# SCH_pcb_tfg_v1_1a_conHDR_2021-07-26.net
KiCad netlist of a schematic drawn in EasyEDA
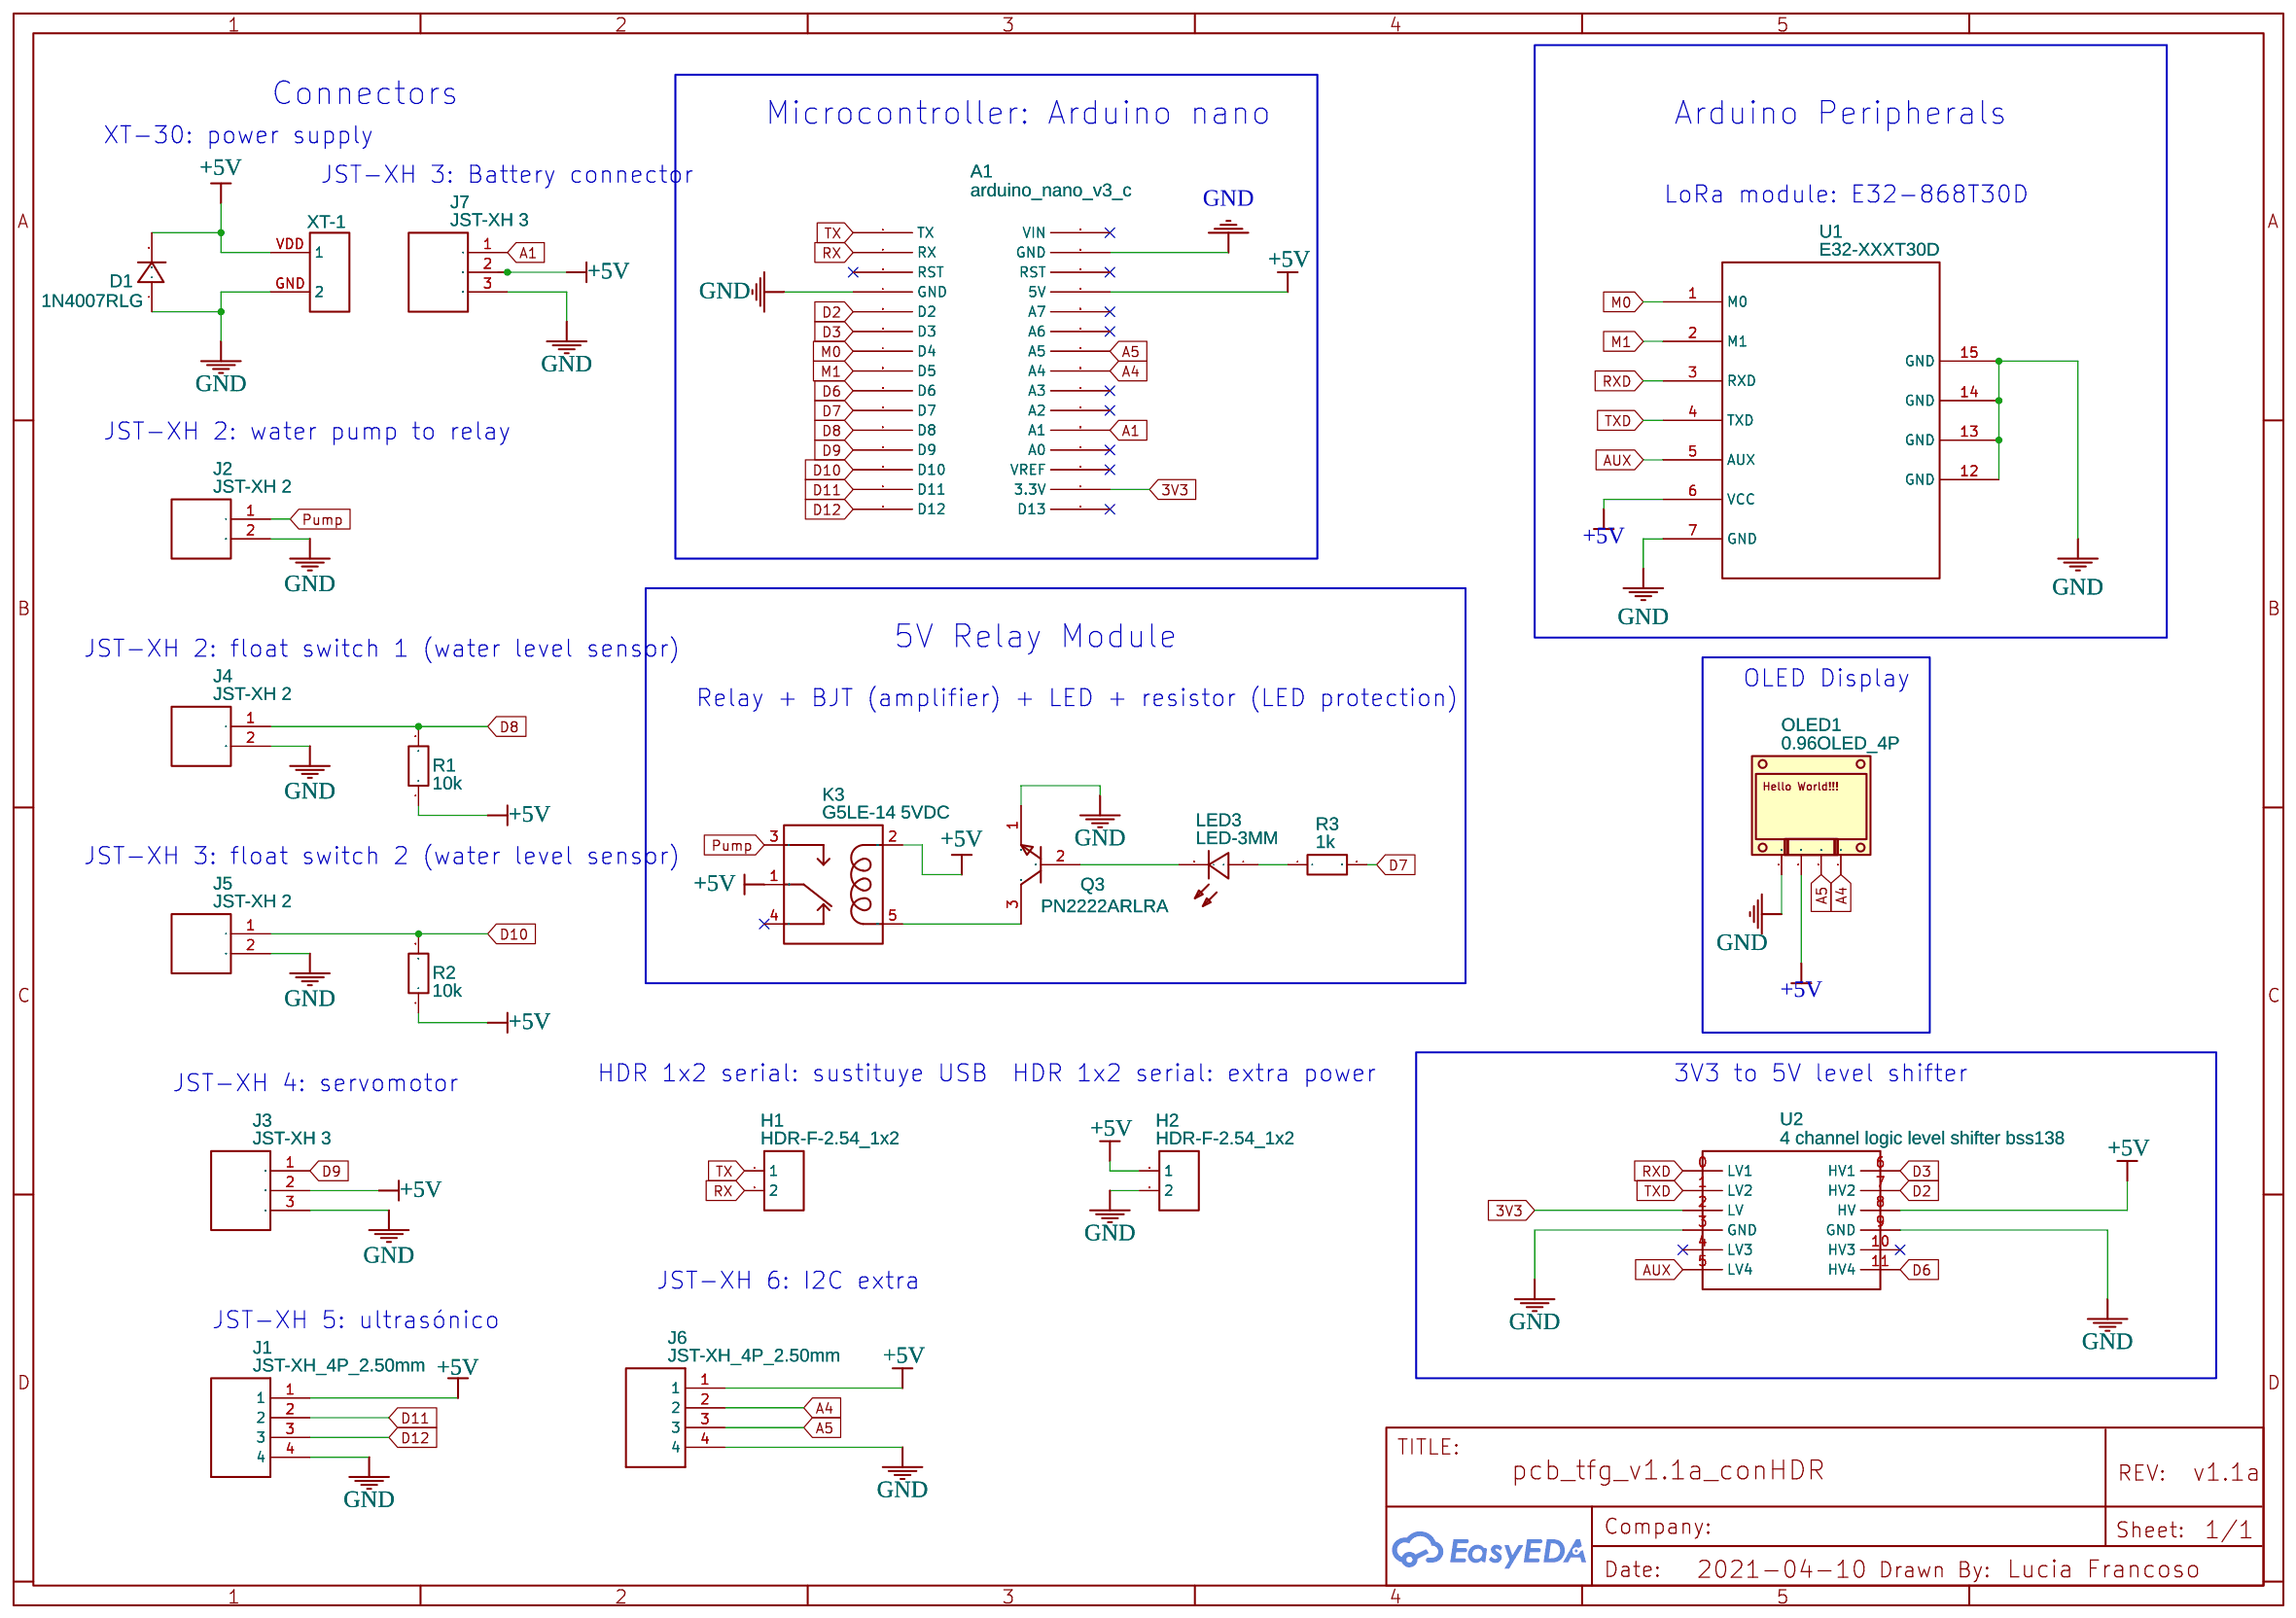
[diagram p0: schematic sheet]

(export (version "E")
  (design (tool "Eeschema 10.0.6"))
  (components
    (comp (ref "A1")
      (value "arduino_nano_v3_с")
      (fields (field (name "BOM_Manufacturer Part") "Arduino Nano"))
      (libsource (lib "") (part "arduino_nano_v3_с"))
    )
    (comp (ref "D1")
      (value "1N4007RLG")
      (fields (field (name "BOM_Supplier Part") "C53568"))
      (libsource (lib "") (part "1N4007RLG"))
    )
    (comp (ref "H1")
      (value "HDR-F-2.54_1x2")
      (fields (field (name "BOM_Supplier Part") "C49661"))
      (libsource (lib "") (part "HDR-F-2.54_1x2"))
    )
    (comp (ref "H2")
      (value "HDR-F-2.54_1x2")
      (fields (field (name "BOM_Supplier Part") "C49661"))
      (libsource (lib "") (part "HDR-F-2.54_1x2"))
    )
    (comp (ref "J1")
      (value "JST-XH_4P_2.50mm")
      (fields (field (name "BOM_Manufacturer Part") "JST"))
      (libsource (lib "") (part "JST-XH_4P_2.50mm"))
    )
    (comp (ref "J2") (value "JST-XH 2") (libsource (lib "") (part "JST-XH 2")))
    (comp (ref "J3")
      (value "JST-XH 3")
      (fields
        (field (name "BOM_Manufacturer Part") "B3B-XH-A(LF)(SN)")
        (field (name "BOM_Supplier Part") "455-2248-ND")
      )
      (libsource (lib "") (part "JST-XH 3"))
    )
    (comp (ref "J4") (value "JST-XH 2") (libsource (lib "") (part "JST-XH 2")))
    (comp (ref "J5") (value "JST-XH 2") (libsource (lib "") (part "JST-XH 2")))
    (comp (ref "J6")
      (value "JST-XH_4P_2.50mm")
      (fields (field (name "BOM_Manufacturer Part") "JST"))
      (libsource (lib "") (part "JST-XH_4P_2.50mm"))
    )
    (comp (ref "J7")
      (value "JST-XH 3")
      (fields
        (field (name "BOM_Manufacturer Part") "B3B-XH-A(LF)(SN)")
        (field (name "BOM_Supplier Part") "455-2248-ND")
      )
      (libsource (lib "") (part "JST-XH 3"))
    )
    (comp (ref "K3")
      (value "G5LE-14 5VDC")
      (fields (field (name "BOM_Supplier Part") "C116963"))
      (libsource (lib "") (part "Unknown_415_-365"))
    )
    (comp (ref "LED3")
      (value "LED-3MM")
      (fields
        (field (name "BOM_Manufacturer Part") "204-10SURD/S530-A3")
        (field (name "BOM_Supplier Part") "C99772")
      )
      (libsource (lib "") (part "Unknown_610_-370"))
    )
    (comp (ref "OLED1") (value "0.96OLED_4P") (libsource (lib "") (part "0.96OLED_4P")))
    (comp (ref "Q3")
      (value "PN2222ARLRA")
      (fields (field (name "BOM_Manufacturer Part") "?"))
      (libsource (lib "") (part "Unknown_525_-375"))
    )
    (comp (ref "R1")
      (value "10k")
      (fields (field (name "BOM_Manufacturer Part") "?"))
      (libsource (lib "") (part "Res_AXIAL-0.3(1/8W)_EU"))
    )
    (comp (ref "R2")
      (value "10k")
      (fields (field (name "BOM_Manufacturer Part") "?"))
      (libsource (lib "") (part "Res_AXIAL-0.3(1/8W)_EU"))
    )
    (comp (ref "R3")
      (value "1k")
      (fields (field (name "BOM_Manufacturer Part") "?"))
      (libsource (lib "") (part "Res_AXIAL-0.3(1/8W)_EU_1"))
    )
    (comp (ref "U1")
      (value "E32-XXXT30D")
      (fields (field (name "BOM_Manufacturer Part") "E32-433T30D (TTL-1W)"))
      (libsource (lib "") (part "E32-XXXT30D"))
    )
    (comp (ref "U2")
      (value "4 channel logic level shifter bss138")
      (libsource (lib "") (part "4 channel logic level shifter bss138"))
    )
    (comp (ref "XT-1")
      (value "Terminal_2P/5.08")
      (fields (field (name "BOM_Manufacturer Part") "Screw terminal 2p"))
      (libsource (lib "") (part "Terminal_2P/5.08"))
    )
  )
  (nets
    (net (code "1") (name "+5V") (class "Default")
      (node (ref "A1") (pin "27") (pinfunction "5V_27") (pintype "unspecified"))
      (node (ref "D1") (pin "C") (pinfunction "C_C") (pintype "unspecified"))
      (node (ref "H2") (pin "1") (pinfunction "1_1") (pintype "input"))
      (node (ref "J1") (pin "1") (pinfunction "1_1") (pintype "unspecified"))
      (node (ref "J3") (pin "2") (pinfunction "2_2") (pintype "unspecified"))
      (node (ref "J6") (pin "1") (pinfunction "1_1") (pintype "unspecified"))
      (node (ref "J7") (pin "2") (pinfunction "2_2") (pintype "unspecified"))
      (node (ref "K3") (pin "1") (pinfunction "MAIN_1") (pintype "unspecified"))
      (node (ref "K3") (pin "2") (pinfunction "COIL2_2") (pintype "unspecified"))
      (node (ref "OLED1") (pin "2") (pinfunction "2_2") (pintype "unspecified"))
      (node (ref "R1") (pin "1") (pinfunction "1_1") (pintype "unspecified"))
      (node (ref "R2") (pin "1") (pinfunction "1_1") (pintype "unspecified"))
      (node (ref "U1") (pin "6") (pinfunction "VCC_6") (pintype "unspecified"))
      (node (ref "U2") (pin "8") (pinfunction "HV_8") (pintype "unspecified"))
      (node (ref "XT-1") (pin "VDD") (pinfunction "1_VDD") (pintype "unspecified"))
    )
    (net (code "2") (name "3V3") (class "Default")
      (node (ref "A1") (pin "17") (pinfunction "3.3V_17") (pintype "unspecified"))
      (node (ref "U2") (pin "2") (pinfunction "LV_2") (pintype "unspecified"))
    )
    (net (code "3") (name "A1") (class "Default")
      (node (ref "A1") (pin "20") (pinfunction "A1_20") (pintype "unspecified"))
      (node (ref "J7") (pin "1") (pinfunction "1_1") (pintype "unspecified"))
    )
    (net (code "4") (name "A4") (class "Default")
      (node (ref "A1") (pin "23") (pinfunction "A4_23") (pintype "unspecified"))
      (node (ref "J6") (pin "2") (pinfunction "2_2") (pintype "unspecified"))
      (node (ref "OLED1") (pin "4") (pinfunction "4_4") (pintype "unspecified"))
    )
    (net (code "5") (name "A5") (class "Default")
      (node (ref "A1") (pin "24") (pinfunction "A5_24") (pintype "unspecified"))
      (node (ref "J6") (pin "3") (pinfunction "3_3") (pintype "unspecified"))
      (node (ref "OLED1") (pin "3") (pinfunction "3_3") (pintype "unspecified"))
    )
    (net (code "6") (name "AUX") (class "Default")
      (node (ref "U1") (pin "5") (pinfunction "AUX_5") (pintype "unspecified"))
      (node (ref "U2") (pin "5") (pinfunction "LV4_5") (pintype "unspecified"))
    )
    (net (code "7") (name "D2") (class "Default")
      (node (ref "A1") (pin "5") (pinfunction "D2_5") (pintype "unspecified"))
      (node (ref "U2") (pin "7") (pinfunction "HV2_7") (pintype "unspecified"))
    )
    (net (code "8") (name "D3") (class "Default")
      (node (ref "A1") (pin "6") (pinfunction "D3_6") (pintype "unspecified"))
      (node (ref "U2") (pin "6") (pinfunction "HV1_6") (pintype "unspecified"))
    )
    (net (code "9") (name "D6") (class "Default")
      (node (ref "A1") (pin "9") (pinfunction "D6_9") (pintype "unspecified"))
      (node (ref "U2") (pin "11") (pinfunction "HV4_11") (pintype "unspecified"))
    )
    (net (code "10") (name "D7") (class "Default")
      (node (ref "A1") (pin "10") (pinfunction "D7_10") (pintype "unspecified"))
      (node (ref "R3") (pin "2") (pinfunction "2_2") (pintype "unspecified"))
    )
    (net (code "11") (name "D8") (class "Default")
      (node (ref "A1") (pin "11") (pinfunction "D8_11") (pintype "unspecified"))
      (node (ref "J4") (pin "1") (pinfunction "1_1") (pintype "unspecified"))
      (node (ref "R1") (pin "2") (pinfunction "2_2") (pintype "unspecified"))
    )
    (net (code "12") (name "D9") (class "Default")
      (node (ref "A1") (pin "12") (pinfunction "D9_12") (pintype "unspecified"))
      (node (ref "J3") (pin "1") (pinfunction "1_1") (pintype "unspecified"))
    )
    (net (code "13") (name "D10") (class "Default")
      (node (ref "A1") (pin "13") (pinfunction "D10_13") (pintype "unspecified"))
      (node (ref "J5") (pin "1") (pinfunction "1_1") (pintype "unspecified"))
      (node (ref "R2") (pin "2") (pinfunction "2_2") (pintype "unspecified"))
    )
    (net (code "14") (name "D11") (class "Default")
      (node (ref "A1") (pin "14") (pinfunction "D11_14") (pintype "unspecified"))
      (node (ref "J1") (pin "2") (pinfunction "2_2") (pintype "unspecified"))
    )
    (net (code "15") (name "D12") (class "Default")
      (node (ref "A1") (pin "15") (pinfunction "D12_15") (pintype "unspecified"))
      (node (ref "J1") (pin "3") (pinfunction "3_3") (pintype "unspecified"))
    )
    (net (code "16") (name "GND") (class "Default")
      (node (ref "A1") (pin "29") (pinfunction "GND_29") (pintype "unspecified"))
      (node (ref "A1") (pin "4") (pinfunction "GND_4") (pintype "unspecified"))
      (node (ref "D1") (pin "A") (pinfunction "A_A") (pintype "unspecified"))
      (node (ref "H2") (pin "2") (pinfunction "2_2") (pintype "input"))
      (node (ref "J1") (pin "4") (pinfunction "4_4") (pintype "unspecified"))
      (node (ref "J2") (pin "2") (pinfunction "2_2") (pintype "unspecified"))
      (node (ref "J3") (pin "3") (pinfunction "2_3") (pintype "unspecified"))
      (node (ref "J4") (pin "2") (pinfunction "2_2") (pintype "unspecified"))
      (node (ref "J5") (pin "2") (pinfunction "2_2") (pintype "unspecified"))
      (node (ref "J6") (pin "4") (pinfunction "4_4") (pintype "unspecified"))
      (node (ref "J7") (pin "3") (pinfunction "2_3") (pintype "unspecified"))
      (node (ref "OLED1") (pin "1") (pinfunction "1_1") (pintype "unspecified"))
      (node (ref "Q3") (pin "1") (pinfunction "E_1") (pintype "unspecified"))
      (node (ref "U1") (pin "12") (pinfunction "GND_12") (pintype "unspecified"))
      (node (ref "U1") (pin "13") (pinfunction "GND_13") (pintype "unspecified"))
      (node (ref "U1") (pin "14") (pinfunction "GND_14") (pintype "unspecified"))
      (node (ref "U1") (pin "15") (pinfunction "GND_15") (pintype "unspecified"))
      (node (ref "U1") (pin "7") (pinfunction "GND_7") (pintype "unspecified"))
      (node (ref "U2") (pin "3") (pinfunction "GND_3") (pintype "unspecified"))
      (node (ref "U2") (pin "9") (pinfunction "GND_9") (pintype "unspecified"))
      (node (ref "XT-1") (pin "GND") (pinfunction "2_GND") (pintype "unspecified"))
    )
    (net (code "17") (name "M0") (class "Default")
      (node (ref "A1") (pin "7") (pinfunction "D4_7") (pintype "unspecified"))
      (node (ref "U1") (pin "1") (pinfunction "M0_1") (pintype "unspecified"))
    )
    (net (code "18") (name "M1") (class "Default")
      (node (ref "A1") (pin "8") (pinfunction "D5_8") (pintype "unspecified"))
      (node (ref "U1") (pin "2") (pinfunction "M1_2") (pintype "unspecified"))
    )
    (net (code "19") (name "Net-(K3-COIL1)") (class "Default")
      (node (ref "K3") (pin "5") (pinfunction "COIL1_5") (pintype "unspecified"))
      (node (ref "Q3") (pin "3") (pinfunction "C_3") (pintype "unspecified"))
    )
    (net (code "20") (name "Net-(LED3-+)") (class "Default")
      (node (ref "LED3") (pin "1") (pinfunction "+_1") (pintype "unspecified"))
      (node (ref "R3") (pin "1") (pinfunction "1_1") (pintype "unspecified"))
    )
    (net (code "21") (name "Net-(LED3--)") (class "Default")
      (node (ref "LED3") (pin "2") (pinfunction "-_2") (pintype "unspecified"))
      (node (ref "Q3") (pin "2") (pinfunction "B_2") (pintype "unspecified"))
    )
    (net (code "22") (name "Pump") (class "Default")
      (node (ref "J2") (pin "1") (pinfunction "1_1") (pintype "unspecified"))
      (node (ref "K3") (pin "3") (pinfunction "NO_3") (pintype "unspecified"))
    )
    (net (code "23") (name "RX") (class "Default")
      (node (ref "A1") (pin "2") (pinfunction "RX_2") (pintype "unspecified"))
      (node (ref "H1") (pin "2") (pinfunction "2_2") (pintype "input"))
    )
    (net (code "24") (name "RXD") (class "Default")
      (node (ref "U1") (pin "3") (pinfunction "RXD_3") (pintype "unspecified"))
      (node (ref "U2") (pin "0") (pinfunction "LV1_0") (pintype "unspecified"))
    )
    (net (code "25") (name "TX") (class "Default")
      (node (ref "A1") (pin "1") (pinfunction "TX_1") (pintype "unspecified"))
      (node (ref "H1") (pin "1") (pinfunction "1_1") (pintype "input"))
    )
    (net (code "26") (name "TXD") (class "Default")
      (node (ref "U1") (pin "4") (pinfunction "TXD_4") (pintype "unspecified"))
      (node (ref "U2") (pin "1") (pinfunction "LV2_1") (pintype "unspecified"))
    )
    (net (code "27") (name "unconnected-(A1-A0-Pad19)") (class "Default")
      (node (ref "A1") (pin "19") (pinfunction "A0_19") (pintype "unspecified+no_connect"))
    )
    (net (code "28") (name "unconnected-(A1-A2-Pad21)") (class "Default")
      (node (ref "A1") (pin "21") (pinfunction "A2_21") (pintype "unspecified+no_connect"))
    )
    (net (code "29") (name "unconnected-(A1-A3-Pad22)") (class "Default")
      (node (ref "A1") (pin "22") (pinfunction "A3_22") (pintype "unspecified+no_connect"))
    )
    (net (code "30") (name "unconnected-(A1-A6-Pad25)") (class "Default")
      (node (ref "A1") (pin "25") (pinfunction "A6_25") (pintype "unspecified+no_connect"))
    )
    (net (code "31") (name "unconnected-(A1-A7-Pad26)") (class "Default")
      (node (ref "A1") (pin "26") (pinfunction "A7_26") (pintype "unspecified+no_connect"))
    )
    (net (code "32") (name "unconnected-(A1-D13-Pad16)") (class "Default")
      (node (ref "A1") (pin "16") (pinfunction "D13_16") (pintype "unspecified+no_connect"))
    )
    (net (code "33") (name "unconnected-(A1-RST-Pad3)") (class "Default")
      (node (ref "A1") (pin "3") (pinfunction "RST_3") (pintype "unspecified+no_connect"))
    )
    (net (code "34") (name "unconnected-(A1-RST-Pad28)") (class "Default")
      (node (ref "A1") (pin "28") (pinfunction "RST_28") (pintype "unspecified+no_connect"))
    )
    (net (code "35") (name "unconnected-(A1-VIN-Pad30)") (class "Default")
      (node (ref "A1") (pin "30") (pinfunction "VIN_30") (pintype "unspecified+no_connect"))
    )
    (net (code "36") (name "unconnected-(A1-VREF-Pad18)") (class "Default")
      (node (ref "A1") (pin "18") (pinfunction "VREF_18") (pintype "unspecified+no_connect"))
    )
    (net (code "37") (name "unconnected-(K3-NC-Pad4)") (class "Default")
      (node (ref "K3") (pin "4") (pinfunction "NC_4") (pintype "unspecified+no_connect"))
    )
    (net (code "38") (name "unconnected-(U2-HV3-Pad10)") (class "Default")
      (node (ref "U2") (pin "10") (pinfunction "HV3_10") (pintype "unspecified+no_connect"))
    )
    (net (code "39") (name "unconnected-(U2-LV3-Pad4)") (class "Default")
      (node (ref "U2") (pin "4") (pinfunction "LV3_4") (pintype "unspecified+no_connect"))
    )
  )
)
